# SCH_SCore-SR1_2024-11-10.net
KiCad netlist of a schematic drawn in EasyEDA
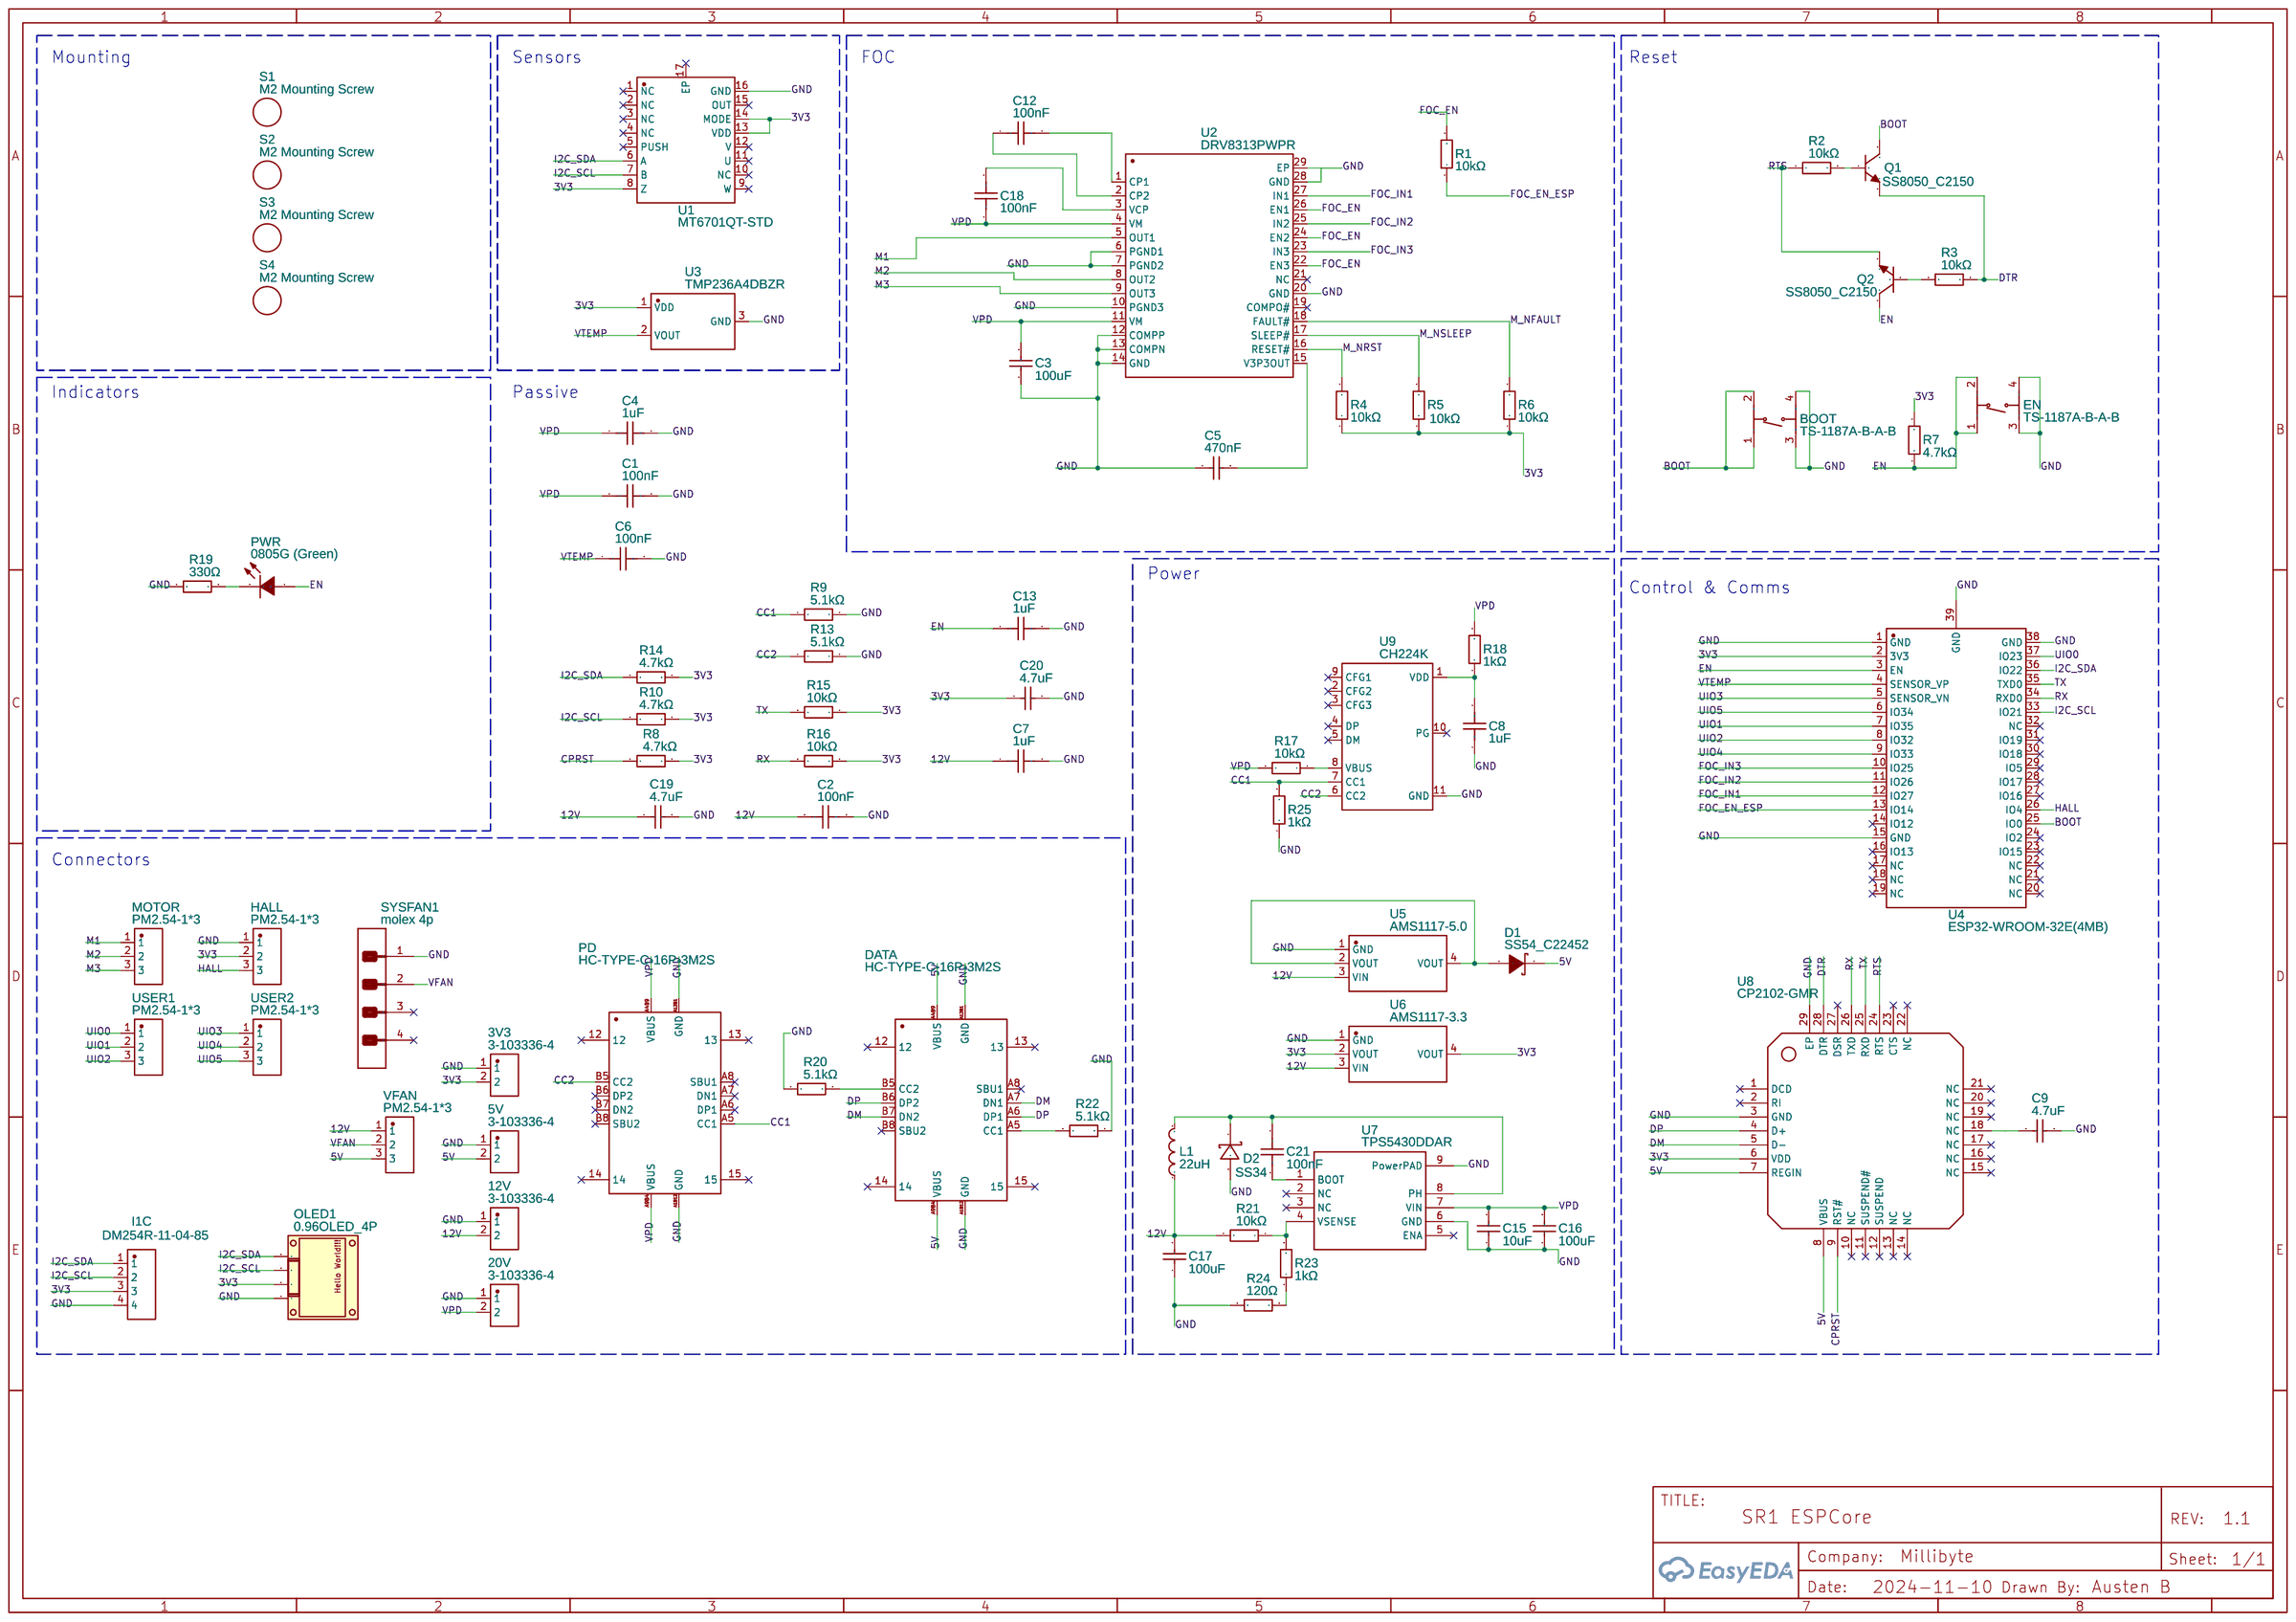
[diagram p0: schematic sheet]

(export (version "E")
  (design (tool "Eeschema 10.0.6"))
  (components
    (comp (ref "3V3")
      (value "3-103336-4")
      (fields (field (name "Manufacturer") "TE Connectivity(泰科电子)"))
      (libsource (lib "") (part "3-103336-4"))
    )
    (comp (ref "5V")
      (value "3-103336-4")
      (fields (field (name "Manufacturer") "TE Connectivity(泰科电子)"))
      (libsource (lib "") (part "3-103336-4_3"))
    )
    (comp (ref "12V")
      (value "3-103336-4")
      (fields (field (name "Manufacturer") "TE Connectivity(泰科电子)"))
      (libsource (lib "") (part "3-103336-4_1"))
    )
    (comp (ref "20V")
      (value "3-103336-4")
      (fields (field (name "Manufacturer") "TE Connectivity(泰科电子)"))
      (libsource (lib "") (part "3-103336-4_2"))
    )
    (comp (ref "BOOT")
      (value "TS-1187A-B-A-B")
      (fields (field (name "Manufacturer") "XKB Connectivity(中国星坤)"))
      (libsource (lib "") (part "TS-1187A-B-A-B"))
    )
    (comp (ref "C1")
      (value "100nF")
      (fields
        (field (name "Manufacturer Part") "CC0603KRX7R9BB104")
        (field (name "Manufacturer") "YAGEO(国巨)")
      )
      (libsource (lib "") (part "CC0603KRX7R9BB104"))
    )
    (comp (ref "C2")
      (value "100nF")
      (fields
        (field (name "Manufacturer Part") "CC0603KRX7R9BB104")
        (field (name "Manufacturer") "YAGEO(国巨)")
      )
      (libsource (lib "") (part "CC0603KRX7R9BB104"))
    )
    (comp (ref "C3")
      (value "100uF")
      (fields
        (field (name "Manufacturer Part") "CL31A107MQHNNNE")
        (field (name "Manufacturer") "SAMSUNG(三星)")
      )
      (libsource (lib "") (part "CL31A107MQHNNNE"))
    )
    (comp (ref "C4")
      (value "1uF")
      (fields
        (field (name "Manufacturer Part") "CL10A105KB8NNNC")
        (field (name "Manufacturer") "SAMSUNG(三星)")
      )
      (libsource (lib "") (part "CL10A105KB8NNNC_1"))
    )
    (comp (ref "C5")
      (value "470nF")
      (fields
        (field (name "Manufacturer Part") "CL21B474KBFNNNE")
        (field (name "Manufacturer") "SAMSUNG(三星)")
      )
      (libsource (lib "") (part "CL21B474KBFNNNE"))
    )
    (comp (ref "C6")
      (value "100nF")
      (fields
        (field (name "Manufacturer Part") "CC0603KRX7R9BB104")
        (field (name "Manufacturer") "YAGEO(国巨)")
      )
      (libsource (lib "") (part "CC0603KRX7R9BB104"))
    )
    (comp (ref "C7")
      (value "1uF")
      (fields
        (field (name "Manufacturer Part") "CL10A105KB8NNNC")
        (field (name "Manufacturer") "SAMSUNG(三星)")
      )
      (libsource (lib "") (part "CL10A105KB8NNNC_1"))
    )
    (comp (ref "C8")
      (value "1uF")
      (fields
        (field (name "Manufacturer Part") "CL10A105KB8NNNC")
        (field (name "Manufacturer") "SAMSUNG(三星)")
      )
      (libsource (lib "") (part "CL10A105KB8NNNC"))
    )
    (comp (ref "C9")
      (value "4.7uF")
      (fields
        (field (name "Manufacturer Part") "CL21A475KAQNNNE")
        (field (name "Manufacturer") "SAMSUNG(三星)")
      )
      (libsource (lib "") (part "CL21A475KAQNNNE"))
    )
    (comp (ref "C12")
      (value "100nF")
      (fields
        (field (name "Manufacturer Part") "CC0603KRX7R9BB104")
        (field (name "Manufacturer") "YAGEO(国巨)")
      )
      (libsource (lib "") (part "CC0603KRX7R9BB104"))
    )
    (comp (ref "C13")
      (value "1uF")
      (fields
        (field (name "Manufacturer Part") "CL10A105KB8NNNC")
        (field (name "Manufacturer") "SAMSUNG(三星)")
      )
      (libsource (lib "") (part "CL10A105KB8NNNC_1"))
    )
    (comp (ref "C15")
      (value "10uF")
      (fields
        (field (name "Manufacturer Part") "CL31A106KBHNNNE")
        (field (name "Manufacturer") "SAMSUNG(三星)")
      )
      (libsource (lib "") (part "CL31A106KBHNNNE"))
    )
    (comp (ref "C16")
      (value "100uF")
      (fields
        (field (name "Manufacturer Part") "CL31A107MQHNNNE")
        (field (name "Manufacturer") "SAMSUNG(三星)")
      )
      (libsource (lib "") (part "CL31A107MQHNNNE"))
    )
    (comp (ref "C17")
      (value "100uF")
      (fields
        (field (name "Manufacturer Part") "CL31A107MQHNNNE")
        (field (name "Manufacturer") "SAMSUNG(三星)")
      )
      (libsource (lib "") (part "CL31A107MQHNNNE"))
    )
    (comp (ref "C18")
      (value "100nF")
      (fields
        (field (name "Manufacturer Part") "CC0603KRX7R9BB104")
        (field (name "Manufacturer") "YAGEO(国巨)")
      )
      (libsource (lib "") (part "CC0603KRX7R9BB104_2"))
    )
    (comp (ref "C19")
      (value "4.7uF")
      (fields
        (field (name "Manufacturer Part") "CL21A475KAQNNNE")
        (field (name "Manufacturer") "SAMSUNG(三星)")
      )
      (libsource (lib "") (part "CL21A475KAQNNNE"))
    )
    (comp (ref "C20")
      (value "4.7uF")
      (fields
        (field (name "Manufacturer Part") "CL21A475KAQNNNE")
        (field (name "Manufacturer") "SAMSUNG(三星)")
      )
      (libsource (lib "") (part "CL21A475KAQNNNE"))
    )
    (comp (ref "C21")
      (value "100nF")
      (fields
        (field (name "Manufacturer Part") "CC0603KRX7R9BB104")
        (field (name "Manufacturer") "YAGEO(国巨)")
      )
      (libsource (lib "") (part "CC0603KRX7R9BB104_1"))
    )
    (comp (ref "D1")
      (value "SS54_C22452")
      (fields (field (name "Manufacturer Part") "SS54") (field (name "Manufacturer") "MDD"))
      (libsource (lib "") (part "SS54_C22452"))
    )
    (comp (ref "D2")
      (value "SS34")
      (fields (field (name "Manufacturer") "MDD(辰达半导体)"))
      (libsource (lib "") (part "SS34_C8678"))
    )
    (comp (ref "DATA")
      (value "HC-TYPE-C-16P-3M2S")
      (fields (field (name "Manufacturer") "HC(虹成电子)"))
      (libsource (lib "") (part "HC-TYPE-C-16P-3M2S"))
    )
    (comp (ref "EN")
      (value "TS-1187A-B-A-B")
      (fields (field (name "Manufacturer") "XKB Connectivity(中国星坤)"))
      (libsource (lib "") (part "TS-1187A-B-A-B_1"))
    )
    (comp (ref "HALL")
      (value "PM2.54-1*3")
      (fields (field (name "Manufacturer") "ZHOURI(洲日)"))
      (libsource (lib "") (part "PM2.54-1*3"))
    )
    (comp (ref "I1C")
      (value "DM254R-11-04-85")
      (fields (field (name "Manufacturer") "DEALON(德艺隆)"))
      (libsource (lib "") (part "DM254R-11-04-85"))
    )
    (comp (ref "L1")
      (value "22uH")
      (fields (field (name "Manufacturer Part") "PRS4018-220MT") (field (name "Manufacturer") "FH(风华)"))
      (libsource (lib "") (part "PRS4018-220MT"))
    )
    (comp (ref "MOTOR")
      (value "PM2.54-1*3")
      (fields (field (name "Manufacturer") "ZHOURI(洲日)"))
      (libsource (lib "") (part "PM2.54-1*3_3"))
    )
    (comp (ref "OLED1") (value "0.96OLED_4P") (libsource (lib "") (part "0.96OLED_4P")))
    (comp (ref "PD")
      (value "HC-TYPE-C-16P-3M2S")
      (fields (field (name "Manufacturer") "HC(虹成电子)"))
      (libsource (lib "") (part "HC-TYPE-C-16P-3M2S_1"))
    )
    (comp (ref "PWR")
      (value "0805G (Green)")
      (fields (field (name "Manufacturer Part") "KT-0805G") (field (name "Manufacturer") "KENTO"))
      (libsource (lib "") (part "0805G (Green)"))
    )
    (comp (ref "Q1")
      (value "SS8050_C2150")
      (fields (field (name "Manufacturer Part") "SS8050") (field (name "Manufacturer") "CJ(江苏长电/长晶)"))
      (libsource (lib "") (part "SS8050_C2150"))
    )
    (comp (ref "Q2")
      (value "SS8050_C2150")
      (fields (field (name "Manufacturer Part") "SS8050") (field (name "Manufacturer") "CJ(江苏长电/长晶)"))
      (libsource (lib "") (part "SS8050_C2150_1"))
    )
    (comp (ref "R1")
      (value "10kΩ")
      (fields (field (name "Manufacturer Part") "0603WAF4701T5E") (field (name "Manufacturer") "UniOhm"))
      (libsource (lib "") (part "0603WAF4701T5E_1"))
    )
    (comp (ref "R2")
      (value "10kΩ")
      (fields
        (field (name "Manufacturer Part") "1206W4F1002T5E")
        (field (name "Manufacturer") "UNI-ROYAL(厚声)")
      )
      (libsource (lib "") (part "1206W4F1002T5E"))
    )
    (comp (ref "R3")
      (value "10kΩ")
      (fields
        (field (name "Manufacturer Part") "1206W4F1002T5E")
        (field (name "Manufacturer") "UNI-ROYAL(厚声)")
      )
      (libsource (lib "") (part "1206W4F1002T5E"))
    )
    (comp (ref "R4")
      (value "10kΩ")
      (fields (field (name "Manufacturer Part") "0603WAF4701T5E") (field (name "Manufacturer") "UniOhm"))
      (libsource (lib "") (part "0603WAF4701T5E_1"))
    )
    (comp (ref "R5")
      (value "10kΩ")
      (fields (field (name "Manufacturer Part") "0603WAF4701T5E") (field (name "Manufacturer") "UniOhm"))
      (libsource (lib "") (part "0603WAF4701T5E_1"))
    )
    (comp (ref "R6")
      (value "10kΩ")
      (fields (field (name "Manufacturer Part") "0603WAF4701T5E") (field (name "Manufacturer") "UniOhm"))
      (libsource (lib "") (part "0603WAF4701T5E_1"))
    )
    (comp (ref "R7")
      (value "4.7kΩ")
      (fields
        (field (name "Manufacturer Part") "0805W8F4701T5E")
        (field (name "Manufacturer") "UNI-ROYAL(厚声)")
      )
      (libsource (lib "") (part "0805W8F4701T5E_1"))
    )
    (comp (ref "R8")
      (value "4.7kΩ")
      (fields
        (field (name "Manufacturer Part") "0805W8F4701T5E")
        (field (name "Manufacturer") "UNI-ROYAL(厚声)")
      )
      (libsource (lib "") (part "0805W8F4701T5E"))
    )
    (comp (ref "R9")
      (value "5.1kΩ")
      (fields
        (field (name "Manufacturer Part") "0603WAF5101T5E")
        (field (name "Manufacturer") "UNI-ROYAL(厚声)")
      )
      (libsource (lib "") (part "0603WAF5101T5E"))
    )
    (comp (ref "R10")
      (value "4.7kΩ")
      (fields
        (field (name "Manufacturer Part") "0805W8F4701T5E")
        (field (name "Manufacturer") "UNI-ROYAL(厚声)")
      )
      (libsource (lib "") (part "0805W8F4701T5E"))
    )
    (comp (ref "R13")
      (value "5.1kΩ")
      (fields
        (field (name "Manufacturer Part") "0603WAF5101T5E")
        (field (name "Manufacturer") "UNI-ROYAL(厚声)")
      )
      (libsource (lib "") (part "0603WAF5101T5E"))
    )
    (comp (ref "R14")
      (value "4.7kΩ")
      (fields
        (field (name "Manufacturer Part") "0805W8F4701T5E")
        (field (name "Manufacturer") "UNI-ROYAL(厚声)")
      )
      (libsource (lib "") (part "0805W8F4701T5E"))
    )
    (comp (ref "R15")
      (value "10kΩ")
      (fields (field (name "Manufacturer Part") "0603WAF4701T5E") (field (name "Manufacturer") "UniOhm"))
      (libsource (lib "") (part "0603WAF4701T5E"))
    )
    (comp (ref "R16")
      (value "10kΩ")
      (fields (field (name "Manufacturer Part") "0603WAF4701T5E") (field (name "Manufacturer") "UniOhm"))
      (libsource (lib "") (part "0603WAF4701T5E"))
    )
    (comp (ref "R17")
      (value "10kΩ")
      (fields (field (name "Manufacturer Part") "0603WAF4701T5E") (field (name "Manufacturer") "UniOhm"))
      (libsource (lib "") (part "0603WAF4701T5E"))
    )
    (comp (ref "R18")
      (value "1kΩ")
      (fields
        (field (name "Manufacturer Part") "0402WGF1001TCE")
        (field (name "Manufacturer") "UNI-ROYAL(厚声)")
      )
      (libsource (lib "") (part "0402WGF1001TCE"))
    )
    (comp (ref "R19")
      (value "330Ω")
      (fields
        (field (name "Manufacturer Part") "0805W8F3300T5E")
        (field (name "Manufacturer") "UNI-ROYAL(厚声)")
      )
      (libsource (lib "") (part "0805W8F3300T5E"))
    )
    (comp (ref "R20")
      (value "5.1kΩ")
      (fields
        (field (name "Manufacturer Part") "0603WAF5101T5E")
        (field (name "Manufacturer") "UNI-ROYAL(厚声)")
      )
      (libsource (lib "") (part "0603WAF5101T5E"))
    )
    (comp (ref "R21")
      (value "10kΩ")
      (fields
        (field (name "Manufacturer Part") "0805W8F1002T5E")
        (field (name "Manufacturer") "UNI-ROYAL(厚声)")
      )
      (libsource (lib "") (part "0805W8F1002T5E"))
    )
    (comp (ref "R22")
      (value "5.1kΩ")
      (fields
        (field (name "Manufacturer Part") "0603WAF5101T5E")
        (field (name "Manufacturer") "UNI-ROYAL(厚声)")
      )
      (libsource (lib "") (part "0603WAF5101T5E"))
    )
    (comp (ref "R23")
      (value "1kΩ")
      (fields
        (field (name "Manufacturer Part") "0402WGF1001TCE")
        (field (name "Manufacturer") "UNI-ROYAL(厚声)")
      )
      (libsource (lib "") (part "0402WGF1001TCE"))
    )
    (comp (ref "R24")
      (value "120Ω")
      (fields
        (field (name "Manufacturer Part") "0805W8F1200T5E")
        (field (name "Manufacturer") "UNI-ROYAL(厚声)")
      )
      (libsource (lib "") (part "0805W8F1200T5E"))
    )
    (comp (ref "R25")
      (value "1kΩ")
      (fields
        (field (name "Manufacturer Part") "0402WGF1001TCE")
        (field (name "Manufacturer") "UNI-ROYAL(厚声)")
      )
      (libsource (lib "") (part "0402WGF1001TCE"))
    )
    (comp (ref "S1") (value "M2 Mounting Screw") (libsource (lib "") (part "M2 Mounting Screw")))
    (comp (ref "S2") (value "M2 Mounting Screw") (libsource (lib "") (part "M2 Mounting Screw")))
    (comp (ref "S3") (value "M2 Mounting Screw") (libsource (lib "") (part "M2 Mounting Screw")))
    (comp (ref "S4") (value "M2 Mounting Screw") (libsource (lib "") (part "M2 Mounting Screw")))
    (comp (ref "SYSFAN1") (value "molex 4p") (libsource (lib "") (part "molex 4p")))
    (comp (ref "U1")
      (value "MT6701QT-STD")
      (fields (field (name "Manufacturer") "MagnTek(麦歌恩)"))
      (libsource (lib "") (part "MT6701QT-STD"))
    )
    (comp (ref "U2")
      (value "DRV8313PWPR")
      (fields (field (name "Manufacturer") "Texas Instruments"))
      (libsource (lib "") (part "DRV8313PWPR"))
    )
    (comp (ref "U3")
      (value "TMP236A4DBZR")
      (fields (field (name "Manufacturer") "TI(德州仪器)"))
      (libsource (lib "") (part "TMP236A4DBZR"))
    )
    (comp (ref "U4")
      (value "ESP32-WROOM-32E(4MB)")
      (fields
        (field (name "Manufacturer Part") "ESP32-WROOM-32E-N4")
        (field (name "Manufacturer") "ESPRESSIF(乐鑫)")
      )
      (libsource (lib "") (part "ESP32-WROOM-32E(4MB)"))
    )
    (comp (ref "U5")
      (value "AMS1117-5.0")
      (fields (field (name "Manufacturer") "AMS"))
      (libsource (lib "") (part "AMS1117-5.0"))
    )
    (comp (ref "U6")
      (value "AMS1117-3.3")
      (fields (field (name "Manufacturer") "AMS"))
      (libsource (lib "") (part "AMS1117-3.3"))
    )
    (comp (ref "U7")
      (value "TPS5430DDAR")
      (fields (field (name "Manufacturer") "TI(德州仪器)"))
      (libsource (lib "") (part "TPS5430DDAR"))
    )
    (comp (ref "U8")
      (value "CP2102-GMR")
      (fields (field (name "Manufacturer") "SKYWORKS/SILICON LABS(芯科)"))
      (libsource (lib "") (part "CP2102-GMR"))
    )
    (comp (ref "U9")
      (value "CH224K")
      (fields (field (name "Manufacturer") "WCH(南京沁恒)"))
      (libsource (lib "") (part "CH224K"))
    )
    (comp (ref "USER1")
      (value "PM2.54-1*3")
      (fields (field (name "Manufacturer") "ZHOURI(洲日)"))
      (libsource (lib "") (part "PM2.54-1*3_2"))
    )
    (comp (ref "USER2")
      (value "PM2.54-1*3")
      (fields (field (name "Manufacturer") "ZHOURI(洲日)"))
      (libsource (lib "") (part "PM2.54-1*3_2"))
    )
    (comp (ref "VFAN")
      (value "PM2.54-1*3")
      (fields (field (name "Manufacturer") "ZHOURI(洲日)"))
      (libsource (lib "") (part "PM2.54-1*3_1"))
    )
  )
  (nets
    (net (code "1") (name "/3V3") (class "Default")
      (node (ref "3V3") (pin "2") (pinfunction "2_2") (pintype "unspecified"))
      (node (ref "C20") (pin "1") (pinfunction "1_1") (pintype "input"))
      (node (ref "HALL") (pin "2") (pinfunction "2_2") (pintype "unspecified"))
      (node (ref "I1C") (pin "3") (pinfunction "3_3") (pintype "unspecified"))
      (node (ref "OLED1") (pin "3") (pinfunction "3_3") (pintype "unspecified"))
      (node (ref "R10") (pin "1") (pinfunction "1_1") (pintype "input"))
      (node (ref "R14") (pin "1") (pinfunction "1_1") (pintype "input"))
      (node (ref "R15") (pin "1") (pinfunction "1_1") (pintype "input"))
      (node (ref "R16") (pin "1") (pinfunction "1_1") (pintype "input"))
      (node (ref "R4") (pin "1") (pinfunction "1_1") (pintype "input"))
      (node (ref "R5") (pin "1") (pinfunction "1_1") (pintype "input"))
      (node (ref "R6") (pin "1") (pinfunction "1_1") (pintype "input"))
      (node (ref "R7") (pin "2") (pinfunction "2_2") (pintype "input"))
      (node (ref "R8") (pin "1") (pinfunction "1_1") (pintype "input"))
      (node (ref "U1") (pin "13") (pinfunction "VDD_13") (pintype "unspecified"))
      (node (ref "U1") (pin "14") (pinfunction "MODE_14") (pintype "unspecified"))
      (node (ref "U1") (pin "8") (pinfunction "Z_8") (pintype "unspecified"))
      (node (ref "U3") (pin "1") (pinfunction "VDD_1") (pintype "unspecified"))
      (node (ref "U4") (pin "2") (pinfunction "3V3_2") (pintype "unspecified"))
      (node (ref "U6") (pin "2") (pinfunction "VOUT_2") (pintype "unspecified"))
      (node (ref "U6") (pin "4") (pinfunction "VOUT_4") (pintype "unspecified"))
      (node (ref "U8") (pin "6") (pinfunction "VDD_6") (pintype "unspecified"))
    )
    (net (code "2") (name "/5V") (class "Default")
      (node (ref "5V") (pin "2") (pinfunction "2_2") (pintype "unspecified"))
      (node (ref "D1") (pin "2") (pinfunction "K_2") (pintype "unspecified"))
      (node (ref "DATA") (pin "A4B9") (pinfunction "VBUS_A4B9") (pintype "unspecified"))
      (node (ref "DATA") (pin "A9B4") (pinfunction "VBUS_A9B4") (pintype "unspecified"))
      (node (ref "U8") (pin "7") (pinfunction "REGIN_7") (pintype "unspecified"))
      (node (ref "U8") (pin "8") (pinfunction "VBUS_8") (pintype "unspecified"))
      (node (ref "VFAN") (pin "3") (pinfunction "3_3") (pintype "unspecified"))
    )
    (net (code "3") (name "/12V") (class "Default")
      (node (ref "12V") (pin "2") (pinfunction "2_2") (pintype "unspecified"))
      (node (ref "C17") (pin "2") (pinfunction "2_2") (pintype "input"))
      (node (ref "C19") (pin "1") (pinfunction "1_1") (pintype "input"))
      (node (ref "C2") (pin "1") (pinfunction "1_1") (pintype "unspecified"))
      (node (ref "C7") (pin "1") (pinfunction "1_1") (pintype "unspecified"))
      (node (ref "L1") (pin "1") (pinfunction "1_1") (pintype "unspecified"))
      (node (ref "R21") (pin "2") (pinfunction "2_2") (pintype "input"))
      (node (ref "U5") (pin "3") (pinfunction "VIN_3") (pintype "unspecified"))
      (node (ref "U6") (pin "3") (pinfunction "VIN_3") (pintype "unspecified"))
      (node (ref "VFAN") (pin "1") (pinfunction "1_1") (pintype "unspecified"))
    )
    (net (code "4") (name "/BOOT") (class "Default")
      (node (ref "BOOT") (pin "1") (pinfunction "A_1") (pintype "unspecified"))
      (node (ref "BOOT") (pin "2") (pinfunction "B_2") (pintype "unspecified"))
      (node (ref "Q1") (pin "3") (pinfunction "C_3") (pintype "unspecified"))
      (node (ref "U4") (pin "25") (pinfunction "IO0_25") (pintype "unspecified"))
    )
    (net (code "5") (name "/CC1") (class "Default")
      (node (ref "PD") (pin "A5") (pinfunction "CC1_A5") (pintype "unspecified"))
      (node (ref "R25") (pin "2") (pinfunction "2_2") (pintype "input"))
      (node (ref "R9") (pin "1") (pinfunction "1_1") (pintype "input"))
      (node (ref "U9") (pin "7") (pinfunction "CC1_7") (pintype "unspecified"))
    )
    (net (code "6") (name "/CC2") (class "Default")
      (node (ref "PD") (pin "B5") (pinfunction "CC2_B5") (pintype "unspecified"))
      (node (ref "R13") (pin "1") (pinfunction "1_1") (pintype "input"))
      (node (ref "U9") (pin "6") (pinfunction "CC2_6") (pintype "unspecified"))
    )
    (net (code "7") (name "/CPRST") (class "Default")
      (node (ref "R8") (pin "2") (pinfunction "2_2") (pintype "input"))
      (node (ref "U8") (pin "9") (pinfunction "RST#_9") (pintype "unspecified"))
    )
    (net (code "8") (name "/DM") (class "Default")
      (node (ref "DATA") (pin "A7") (pinfunction "DN1_A7") (pintype "unspecified"))
      (node (ref "DATA") (pin "B7") (pinfunction "DN2_B7") (pintype "unspecified"))
      (node (ref "U8") (pin "5") (pinfunction "D-_5") (pintype "unspecified"))
    )
    (net (code "9") (name "/DP") (class "Default")
      (node (ref "DATA") (pin "A6") (pinfunction "DP1_A6") (pintype "unspecified"))
      (node (ref "DATA") (pin "B6") (pinfunction "DP2_B6") (pintype "unspecified"))
      (node (ref "U8") (pin "4") (pinfunction "D+_4") (pintype "unspecified"))
    )
    (net (code "10") (name "/DTR") (class "Default")
      (node (ref "Q1") (pin "2") (pinfunction "E_2") (pintype "unspecified"))
      (node (ref "R3") (pin "2") (pinfunction "2_2") (pintype "input"))
      (node (ref "U8") (pin "28") (pinfunction "DTR_28") (pintype "unspecified"))
    )
    (net (code "11") (name "/EN") (class "Default")
      (node (ref "C13") (pin "1") (pinfunction "1_1") (pintype "unspecified"))
      (node (ref "EN") (pin "1") (pinfunction "A_1") (pintype "unspecified"))
      (node (ref "EN") (pin "2") (pinfunction "B_2") (pintype "unspecified"))
      (node (ref "PWR") (pin "1") (pinfunction "A_1") (pintype "unspecified"))
      (node (ref "Q2") (pin "3") (pinfunction "C_3") (pintype "unspecified"))
      (node (ref "R7") (pin "1") (pinfunction "1_1") (pintype "input"))
      (node (ref "U4") (pin "3") (pinfunction "EN_3") (pintype "unspecified"))
    )
    (net (code "12") (name "/FOC_EN") (class "Default")
      (node (ref "R1") (pin "2") (pinfunction "2_2") (pintype "input"))
      (node (ref "U2") (pin "22") (pinfunction "EN3_22") (pintype "unspecified"))
      (node (ref "U2") (pin "24") (pinfunction "EN2_24") (pintype "unspecified"))
      (node (ref "U2") (pin "26") (pinfunction "EN1_26") (pintype "unspecified"))
    )
    (net (code "13") (name "/FOC_EN_ESP") (class "Default")
      (node (ref "R1") (pin "1") (pinfunction "1_1") (pintype "input"))
      (node (ref "U4") (pin "13") (pinfunction "IO14_13") (pintype "unspecified"))
    )
    (net (code "14") (name "/FOC_IN1") (class "Default")
      (node (ref "U2") (pin "27") (pinfunction "IN1_27") (pintype "unspecified"))
      (node (ref "U4") (pin "12") (pinfunction "IO27_12") (pintype "unspecified"))
    )
    (net (code "15") (name "/FOC_IN2") (class "Default")
      (node (ref "U2") (pin "25") (pinfunction "IN2_25") (pintype "unspecified"))
      (node (ref "U4") (pin "11") (pinfunction "IO26_11") (pintype "unspecified"))
    )
    (net (code "16") (name "/FOC_IN3") (class "Default")
      (node (ref "U2") (pin "23") (pinfunction "IN3_23") (pintype "unspecified"))
      (node (ref "U4") (pin "10") (pinfunction "IO25_10") (pintype "unspecified"))
    )
    (net (code "17") (name "/GND") (class "Default")
      (node (ref "12V") (pin "1") (pinfunction "1_1") (pintype "unspecified"))
      (node (ref "20V") (pin "1") (pinfunction "1_1") (pintype "unspecified"))
      (node (ref "3V3") (pin "1") (pinfunction "1_1") (pintype "unspecified"))
      (node (ref "5V") (pin "1") (pinfunction "1_1") (pintype "unspecified"))
      (node (ref "BOOT") (pin "3") (pinfunction "C_3") (pintype "unspecified"))
      (node (ref "BOOT") (pin "4") (pinfunction "D_4") (pintype "unspecified"))
      (node (ref "C1") (pin "2") (pinfunction "2_2") (pintype "unspecified"))
      (node (ref "C13") (pin "2") (pinfunction "2_2") (pintype "unspecified"))
      (node (ref "C15") (pin "1") (pinfunction "1_1") (pintype "input"))
      (node (ref "C16") (pin "1") (pinfunction "1_1") (pintype "input"))
      (node (ref "C17") (pin "1") (pinfunction "1_1") (pintype "input"))
      (node (ref "C19") (pin "2") (pinfunction "2_2") (pintype "input"))
      (node (ref "C2") (pin "2") (pinfunction "2_2") (pintype "unspecified"))
      (node (ref "C20") (pin "2") (pinfunction "2_2") (pintype "input"))
      (node (ref "C3") (pin "1") (pinfunction "1_1") (pintype "input"))
      (node (ref "C4") (pin "2") (pinfunction "2_2") (pintype "unspecified"))
      (node (ref "C5") (pin "1") (pinfunction "1_1") (pintype "unspecified"))
      (node (ref "C6") (pin "2") (pinfunction "2_2") (pintype "unspecified"))
      (node (ref "C7") (pin "2") (pinfunction "2_2") (pintype "unspecified"))
      (node (ref "C8") (pin "1") (pinfunction "1_1") (pintype "unspecified"))
      (node (ref "C9") (pin "2") (pinfunction "2_2") (pintype "input"))
      (node (ref "D2") (pin "2") (pinfunction "A_2") (pintype "unspecified"))
      (node (ref "DATA") (pin "A12B1") (pinfunction "GND_A12B1") (pintype "unspecified"))
      (node (ref "DATA") (pin "A1B12") (pinfunction "GND_A1B12") (pintype "unspecified"))
      (node (ref "EN") (pin "3") (pinfunction "C_3") (pintype "unspecified"))
      (node (ref "EN") (pin "4") (pinfunction "D_4") (pintype "unspecified"))
      (node (ref "HALL") (pin "1") (pinfunction "1_1") (pintype "unspecified"))
      (node (ref "I1C") (pin "4") (pinfunction "4_4") (pintype "unspecified"))
      (node (ref "OLED1") (pin "4") (pinfunction "4_4") (pintype "unspecified"))
      (node (ref "PD") (pin "A12B1") (pinfunction "GND_A12B1") (pintype "unspecified"))
      (node (ref "PD") (pin "A1B12") (pinfunction "GND_A1B12") (pintype "unspecified"))
      (node (ref "R13") (pin "2") (pinfunction "2_2") (pintype "input"))
      (node (ref "R19") (pin "1") (pinfunction "1_1") (pintype "input"))
      (node (ref "R20") (pin "1") (pinfunction "1_1") (pintype "input"))
      (node (ref "R22") (pin "2") (pinfunction "2_2") (pintype "input"))
      (node (ref "R24") (pin "1") (pinfunction "1_1") (pintype "input"))
      (node (ref "R25") (pin "1") (pinfunction "1_1") (pintype "input"))
      (node (ref "R9") (pin "2") (pinfunction "2_2") (pintype "input"))
      (node (ref "SYSFAN1") (pin "1") (pinfunction "1_1") (pintype "bidirectional"))
      (node (ref "U1") (pin "16") (pinfunction "GND_16") (pintype "unspecified"))
      (node (ref "U2") (pin "10") (pinfunction "PGND3_10") (pintype "unspecified"))
      (node (ref "U2") (pin "12") (pinfunction "COMPP_12") (pintype "unspecified"))
      (node (ref "U2") (pin "13") (pinfunction "COMPN_13") (pintype "unspecified"))
      (node (ref "U2") (pin "14") (pinfunction "GND_14") (pintype "unspecified"))
      (node (ref "U2") (pin "20") (pinfunction "GND_20") (pintype "unspecified"))
      (node (ref "U2") (pin "28") (pinfunction "GND_28") (pintype "unspecified"))
      (node (ref "U2") (pin "29") (pinfunction "EP_29") (pintype "unspecified"))
      (node (ref "U2") (pin "6") (pinfunction "PGND1_6") (pintype "unspecified"))
      (node (ref "U2") (pin "7") (pinfunction "PGND2_7") (pintype "unspecified"))
      (node (ref "U3") (pin "3") (pinfunction "GND_3") (pintype "unspecified"))
      (node (ref "U4") (pin "1") (pinfunction "GND_1") (pintype "unspecified"))
      (node (ref "U4") (pin "15") (pinfunction "GND_15") (pintype "unspecified"))
      (node (ref "U4") (pin "38") (pinfunction "GND_38") (pintype "unspecified"))
      (node (ref "U4") (pin "39") (pinfunction "GND_39") (pintype "unspecified"))
      (node (ref "U5") (pin "1") (pinfunction "GND_1") (pintype "unspecified"))
      (node (ref "U6") (pin "1") (pinfunction "GND_1") (pintype "unspecified"))
      (node (ref "U7") (pin "6") (pinfunction "GND_6") (pintype "unspecified"))
      (node (ref "U7") (pin "9") (pinfunction "PowerPAD_9") (pintype "unspecified"))
      (node (ref "U8") (pin "29") (pinfunction "EP_29") (pintype "unspecified"))
      (node (ref "U8") (pin "3") (pinfunction "GND_3") (pintype "unspecified"))
      (node (ref "U9") (pin "11") (pinfunction "GND_11") (pintype "unspecified"))
    )
    (net (code "18") (name "/HALL") (class "Default")
      (node (ref "HALL") (pin "3") (pinfunction "3_3") (pintype "unspecified"))
      (node (ref "U4") (pin "26") (pinfunction "IO4_26") (pintype "unspecified"))
    )
    (net (code "19") (name "/I2C_SCL") (class "Default")
      (node (ref "I1C") (pin "2") (pinfunction "2_2") (pintype "unspecified"))
      (node (ref "OLED1") (pin "2") (pinfunction "2_2") (pintype "unspecified"))
      (node (ref "R10") (pin "2") (pinfunction "2_2") (pintype "input"))
      (node (ref "U1") (pin "7") (pinfunction "B_7") (pintype "unspecified"))
      (node (ref "U4") (pin "33") (pinfunction "IO21_33") (pintype "unspecified"))
    )
    (net (code "20") (name "/I2C_SDA") (class "Default")
      (node (ref "I1C") (pin "1") (pinfunction "1_1") (pintype "unspecified"))
      (node (ref "OLED1") (pin "1") (pinfunction "1_1") (pintype "unspecified"))
      (node (ref "R14") (pin "2") (pinfunction "2_2") (pintype "input"))
      (node (ref "U1") (pin "6") (pinfunction "A_6") (pintype "unspecified"))
      (node (ref "U4") (pin "36") (pinfunction "IO22_36") (pintype "unspecified"))
    )
    (net (code "21") (name "/M1") (class "Default")
      (node (ref "MOTOR") (pin "1") (pinfunction "1_1") (pintype "unspecified"))
      (node (ref "U2") (pin "5") (pinfunction "OUT1_5") (pintype "unspecified"))
    )
    (net (code "22") (name "/M2") (class "Default")
      (node (ref "MOTOR") (pin "2") (pinfunction "2_2") (pintype "unspecified"))
      (node (ref "U2") (pin "8") (pinfunction "OUT2_8") (pintype "unspecified"))
    )
    (net (code "23") (name "/M3") (class "Default")
      (node (ref "MOTOR") (pin "3") (pinfunction "3_3") (pintype "unspecified"))
      (node (ref "U2") (pin "9") (pinfunction "OUT3_9") (pintype "unspecified"))
    )
    (net (code "24") (name "/M_NFAULT") (class "Default")
      (node (ref "R6") (pin "2") (pinfunction "2_2") (pintype "input"))
      (node (ref "U2") (pin "18") (pinfunction "FAULT#_18") (pintype "unspecified"))
    )
    (net (code "25") (name "/M_NRST") (class "Default")
      (node (ref "R4") (pin "2") (pinfunction "2_2") (pintype "input"))
      (node (ref "U2") (pin "16") (pinfunction "RESET#_16") (pintype "unspecified"))
    )
    (net (code "26") (name "/M_NSLEEP") (class "Default")
      (node (ref "R5") (pin "2") (pinfunction "2_2") (pintype "input"))
      (node (ref "U2") (pin "17") (pinfunction "SLEEP#_17") (pintype "unspecified"))
    )
    (net (code "27") (name "/RTS") (class "Default")
      (node (ref "Q2") (pin "2") (pinfunction "E_2") (pintype "unspecified"))
      (node (ref "R2") (pin "1") (pinfunction "1_1") (pintype "input"))
      (node (ref "U8") (pin "24") (pinfunction "RTS_24") (pintype "unspecified"))
    )
    (net (code "28") (name "/RX") (class "Default")
      (node (ref "R16") (pin "2") (pinfunction "2_2") (pintype "input"))
      (node (ref "U4") (pin "34") (pinfunction "RXD0_34") (pintype "unspecified"))
      (node (ref "U8") (pin "26") (pinfunction "TXD_26") (pintype "unspecified"))
    )
    (net (code "29") (name "/TX") (class "Default")
      (node (ref "R15") (pin "2") (pinfunction "2_2") (pintype "input"))
      (node (ref "U4") (pin "35") (pinfunction "TXD0_35") (pintype "unspecified"))
      (node (ref "U8") (pin "25") (pinfunction "RXD_25") (pintype "unspecified"))
    )
    (net (code "30") (name "/UIO0") (class "Default")
      (node (ref "U4") (pin "37") (pinfunction "IO23_37") (pintype "unspecified"))
      (node (ref "USER1") (pin "1") (pinfunction "1_1") (pintype "unspecified"))
    )
    (net (code "31") (name "/UIO1") (class "Default")
      (node (ref "U4") (pin "7") (pinfunction "IO35_7") (pintype "unspecified"))
      (node (ref "USER1") (pin "2") (pinfunction "2_2") (pintype "unspecified"))
    )
    (net (code "32") (name "/UIO2") (class "Default")
      (node (ref "U4") (pin "8") (pinfunction "IO32_8") (pintype "unspecified"))
      (node (ref "USER1") (pin "3") (pinfunction "3_3") (pintype "unspecified"))
    )
    (net (code "33") (name "/UIO3") (class "Default")
      (node (ref "U4") (pin "5") (pinfunction "SENSOR_VN_5") (pintype "unspecified"))
      (node (ref "USER2") (pin "1") (pinfunction "1_1") (pintype "unspecified"))
    )
    (net (code "34") (name "/UIO4") (class "Default")
      (node (ref "U4") (pin "9") (pinfunction "IO33_9") (pintype "unspecified"))
      (node (ref "USER2") (pin "2") (pinfunction "2_2") (pintype "unspecified"))
    )
    (net (code "35") (name "/UIO5") (class "Default")
      (node (ref "U4") (pin "6") (pinfunction "IO34_6") (pintype "unspecified"))
      (node (ref "USER2") (pin "3") (pinfunction "3_3") (pintype "unspecified"))
    )
    (net (code "36") (name "/VFAN") (class "Default")
      (node (ref "SYSFAN1") (pin "2") (pinfunction "2_2") (pintype "bidirectional"))
      (node (ref "VFAN") (pin "2") (pinfunction "2_2") (pintype "unspecified"))
    )
    (net (code "37") (name "/VPD") (class "Default")
      (node (ref "20V") (pin "2") (pinfunction "2_2") (pintype "unspecified"))
      (node (ref "C1") (pin "1") (pinfunction "1_1") (pintype "unspecified"))
      (node (ref "C15") (pin "2") (pinfunction "2_2") (pintype "input"))
      (node (ref "C16") (pin "2") (pinfunction "2_2") (pintype "input"))
      (node (ref "C18") (pin "1") (pinfunction "1_1") (pintype "unspecified"))
      (node (ref "C3") (pin "2") (pinfunction "2_2") (pintype "input"))
      (node (ref "C4") (pin "1") (pinfunction "1_1") (pintype "unspecified"))
      (node (ref "PD") (pin "A4B9") (pinfunction "VBUS_A4B9") (pintype "unspecified"))
      (node (ref "PD") (pin "A9B4") (pinfunction "VBUS_A9B4") (pintype "unspecified"))
      (node (ref "R17") (pin "2") (pinfunction "2_2") (pintype "input"))
      (node (ref "R18") (pin "2") (pinfunction "2_2") (pintype "input"))
      (node (ref "U2") (pin "11") (pinfunction "VM_11") (pintype "unspecified"))
      (node (ref "U2") (pin "4") (pinfunction "VM_4") (pintype "unspecified"))
      (node (ref "U7") (pin "7") (pinfunction "VIN_7") (pintype "unspecified"))
    )
    (net (code "38") (name "/VTEMP") (class "Default")
      (node (ref "C6") (pin "1") (pinfunction "1_1") (pintype "unspecified"))
      (node (ref "U3") (pin "2") (pinfunction "VOUT_2") (pintype "unspecified"))
      (node (ref "U4") (pin "4") (pinfunction "SENSOR_VP_4") (pintype "unspecified"))
    )
    (net (code "39") (name "Net-(C9-Pad1)") (class "Default")
      (node (ref "C9") (pin "1") (pinfunction "1_1") (pintype "input"))
      (node (ref "U8") (pin "18") (pinfunction "NC_18") (pintype "unspecified"))
    )
    (net (code "40") (name "Net-(D1-A)") (class "Default")
      (node (ref "D1") (pin "1") (pinfunction "A_1") (pintype "unspecified"))
      (node (ref "U5") (pin "2") (pinfunction "VOUT_2") (pintype "unspecified"))
      (node (ref "U5") (pin "4") (pinfunction "VOUT_4") (pintype "unspecified"))
    )
    (net (code "41") (name "Net-(D2-K)") (class "Default")
      (node (ref "C21") (pin "1") (pinfunction "1_1") (pintype "unspecified"))
      (node (ref "D2") (pin "1") (pinfunction "K_1") (pintype "unspecified"))
      (node (ref "L1") (pin "2") (pinfunction "2_2") (pintype "unspecified"))
      (node (ref "U7") (pin "8") (pinfunction "PH_8") (pintype "unspecified"))
    )
    (net (code "42") (name "Net-(DATA-CC1)") (class "Default")
      (node (ref "DATA") (pin "A5") (pinfunction "CC1_A5") (pintype "unspecified"))
      (node (ref "R22") (pin "1") (pinfunction "1_1") (pintype "input"))
    )
    (net (code "43") (name "Net-(DATA-CC2)") (class "Default")
      (node (ref "DATA") (pin "B5") (pinfunction "CC2_B5") (pintype "unspecified"))
      (node (ref "R20") (pin "2") (pinfunction "2_2") (pintype "input"))
    )
    (net (code "44") (name "Net-(PWR-K)") (class "Default")
      (node (ref "PWR") (pin "2") (pinfunction "K_2") (pintype "unspecified"))
      (node (ref "R19") (pin "2") (pinfunction "2_2") (pintype "input"))
    )
    (net (code "45") (name "Net-(Q1-B)") (class "Default")
      (node (ref "Q1") (pin "1") (pinfunction "B_1") (pintype "unspecified"))
      (node (ref "R2") (pin "2") (pinfunction "2_2") (pintype "input"))
    )
    (net (code "46") (name "Net-(Q2-B)") (class "Default")
      (node (ref "Q2") (pin "1") (pinfunction "B_1") (pintype "unspecified"))
      (node (ref "R3") (pin "1") (pinfunction "1_1") (pintype "input"))
    )
    (net (code "47") (name "Net-(R23-Pad1)") (class "Default")
      (node (ref "R23") (pin "1") (pinfunction "1_1") (pintype "input"))
      (node (ref "R24") (pin "2") (pinfunction "2_2") (pintype "input"))
    )
    (net (code "48") (name "Net-(U2-CP1)") (class "Default")
      (node (ref "C12") (pin "2") (pinfunction "2_2") (pintype "unspecified"))
      (node (ref "U2") (pin "1") (pinfunction "CP1_1") (pintype "unspecified"))
    )
    (net (code "49") (name "Net-(U2-CP2)") (class "Default")
      (node (ref "C12") (pin "1") (pinfunction "1_1") (pintype "unspecified"))
      (node (ref "U2") (pin "2") (pinfunction "CP2_2") (pintype "unspecified"))
    )
    (net (code "50") (name "Net-(U2-V3P3OUT)") (class "Default")
      (node (ref "C5") (pin "2") (pinfunction "2_2") (pintype "unspecified"))
      (node (ref "U2") (pin "15") (pinfunction "V3P3OUT_15") (pintype "unspecified"))
    )
    (net (code "51") (name "Net-(U2-VCP)") (class "Default")
      (node (ref "C18") (pin "2") (pinfunction "2_2") (pintype "unspecified"))
      (node (ref "U2") (pin "3") (pinfunction "VCP_3") (pintype "unspecified"))
    )
    (net (code "52") (name "Net-(U7-BOOT)") (class "Default")
      (node (ref "C21") (pin "2") (pinfunction "2_2") (pintype "unspecified"))
      (node (ref "U7") (pin "1") (pinfunction "BOOT_1") (pintype "unspecified"))
    )
    (net (code "53") (name "Net-(U7-VSENSE)") (class "Default")
      (node (ref "R21") (pin "1") (pinfunction "1_1") (pintype "input"))
      (node (ref "R23") (pin "2") (pinfunction "2_2") (pintype "input"))
      (node (ref "U7") (pin "4") (pinfunction "VSENSE_4") (pintype "unspecified"))
    )
    (net (code "54") (name "Net-(U9-VBUS)") (class "Default")
      (node (ref "R17") (pin "1") (pinfunction "1_1") (pintype "input"))
      (node (ref "U9") (pin "8") (pinfunction "VBUS_8") (pintype "unspecified"))
    )
    (net (code "55") (name "Net-(U9-VDD)") (class "Default")
      (node (ref "C8") (pin "2") (pinfunction "2_2") (pintype "unspecified"))
      (node (ref "R18") (pin "1") (pinfunction "1_1") (pintype "input"))
      (node (ref "U9") (pin "1") (pinfunction "VDD_1") (pintype "unspecified"))
    )
    (net (code "56") (name "unconnected-(DATA-Pad12)") (class "Default")
      (node (ref "DATA") (pin "12") (pinfunction "12_12") (pintype "unspecified+no_connect"))
    )
    (net (code "57") (name "unconnected-(DATA-Pad13)") (class "Default")
      (node (ref "DATA") (pin "13") (pinfunction "13_13") (pintype "unspecified+no_connect"))
    )
    (net (code "58") (name "unconnected-(DATA-Pad14)") (class "Default")
      (node (ref "DATA") (pin "14") (pinfunction "14_14") (pintype "unspecified+no_connect"))
    )
    (net (code "59") (name "unconnected-(DATA-Pad15)") (class "Default")
      (node (ref "DATA") (pin "15") (pinfunction "15_15") (pintype "unspecified+no_connect"))
    )
    (net (code "60") (name "unconnected-(DATA-SBU1-PadA8)") (class "Default")
      (node (ref "DATA") (pin "A8") (pinfunction "SBU1_A8") (pintype "unspecified+no_connect"))
    )
    (net (code "61") (name "unconnected-(DATA-SBU2-PadB8)") (class "Default")
      (node (ref "DATA") (pin "B8") (pinfunction "SBU2_B8") (pintype "unspecified+no_connect"))
    )
    (net (code "62") (name "unconnected-(PD-DN1-PadA7)") (class "Default")
      (node (ref "PD") (pin "A7") (pinfunction "DN1_A7") (pintype "unspecified+no_connect"))
    )
    (net (code "63") (name "unconnected-(PD-DN2-PadB7)") (class "Default")
      (node (ref "PD") (pin "B7") (pinfunction "DN2_B7") (pintype "unspecified+no_connect"))
    )
    (net (code "64") (name "unconnected-(PD-DP1-PadA6)") (class "Default")
      (node (ref "PD") (pin "A6") (pinfunction "DP1_A6") (pintype "unspecified+no_connect"))
    )
    (net (code "65") (name "unconnected-(PD-DP2-PadB6)") (class "Default")
      (node (ref "PD") (pin "B6") (pinfunction "DP2_B6") (pintype "unspecified+no_connect"))
    )
    (net (code "66") (name "unconnected-(PD-Pad12)") (class "Default")
      (node (ref "PD") (pin "12") (pinfunction "12_12") (pintype "unspecified+no_connect"))
    )
    (net (code "67") (name "unconnected-(PD-Pad13)") (class "Default")
      (node (ref "PD") (pin "13") (pinfunction "13_13") (pintype "unspecified+no_connect"))
    )
    (net (code "68") (name "unconnected-(PD-Pad14)") (class "Default")
      (node (ref "PD") (pin "14") (pinfunction "14_14") (pintype "unspecified+no_connect"))
    )
    (net (code "69") (name "unconnected-(PD-Pad15)") (class "Default")
      (node (ref "PD") (pin "15") (pinfunction "15_15") (pintype "unspecified+no_connect"))
    )
    (net (code "70") (name "unconnected-(PD-SBU1-PadA8)") (class "Default")
      (node (ref "PD") (pin "A8") (pinfunction "SBU1_A8") (pintype "unspecified+no_connect"))
    )
    (net (code "71") (name "unconnected-(PD-SBU2-PadB8)") (class "Default")
      (node (ref "PD") (pin "B8") (pinfunction "SBU2_B8") (pintype "unspecified+no_connect"))
    )
    (net (code "72") (name "unconnected-(SYSFAN1-Pad3)") (class "Default")
      (node (ref "SYSFAN1") (pin "3") (pinfunction "3_3") (pintype "bidirectional+no_connect"))
    )
    (net (code "73") (name "unconnected-(SYSFAN1-Pad4)") (class "Default")
      (node (ref "SYSFAN1") (pin "4") (pinfunction "4_4") (pintype "bidirectional+no_connect"))
    )
    (net (code "74") (name "unconnected-(U1-EP-Pad17)") (class "Default")
      (node (ref "U1") (pin "17") (pinfunction "EP_17") (pintype "unspecified+no_connect"))
    )
    (net (code "75") (name "unconnected-(U1-NC-Pad1)") (class "Default")
      (node (ref "U1") (pin "1") (pinfunction "NC_1") (pintype "unspecified+no_connect"))
    )
    (net (code "76") (name "unconnected-(U1-NC-Pad2)") (class "Default")
      (node (ref "U1") (pin "2") (pinfunction "NC_2") (pintype "unspecified+no_connect"))
    )
    (net (code "77") (name "unconnected-(U1-NC-Pad3)") (class "Default")
      (node (ref "U1") (pin "3") (pinfunction "NC_3") (pintype "unspecified+no_connect"))
    )
    (net (code "78") (name "unconnected-(U1-NC-Pad4)") (class "Default")
      (node (ref "U1") (pin "4") (pinfunction "NC_4") (pintype "unspecified+no_connect"))
    )
    (net (code "79") (name "unconnected-(U1-NC-Pad10)") (class "Default")
      (node (ref "U1") (pin "10") (pinfunction "NC_10") (pintype "unspecified+no_connect"))
    )
    (net (code "80") (name "unconnected-(U1-OUT-Pad15)") (class "Default")
      (node (ref "U1") (pin "15") (pinfunction "OUT_15") (pintype "unspecified+no_connect"))
    )
    (net (code "81") (name "unconnected-(U1-PUSH-Pad5)") (class "Default")
      (node (ref "U1") (pin "5") (pinfunction "PUSH_5") (pintype "unspecified+no_connect"))
    )
    (net (code "82") (name "unconnected-(U1-U-Pad11)") (class "Default")
      (node (ref "U1") (pin "11") (pinfunction "U_11") (pintype "unspecified+no_connect"))
    )
    (net (code "83") (name "unconnected-(U1-V-Pad12)") (class "Default")
      (node (ref "U1") (pin "12") (pinfunction "V_12") (pintype "unspecified+no_connect"))
    )
    (net (code "84") (name "unconnected-(U1-W-Pad9)") (class "Default")
      (node (ref "U1") (pin "9") (pinfunction "W_9") (pintype "unspecified+no_connect"))
    )
    (net (code "85") (name "unconnected-(U2-COMPO#-Pad19)") (class "Default")
      (node (ref "U2") (pin "19") (pinfunction "COMPO#_19") (pintype "unspecified+no_connect"))
    )
    (net (code "86") (name "unconnected-(U2-NC-Pad21)") (class "Default")
      (node (ref "U2") (pin "21") (pinfunction "NC_21") (pintype "unspecified+no_connect"))
    )
    (net (code "87") (name "unconnected-(U4-IO2-Pad24)") (class "Default")
      (node (ref "U4") (pin "24") (pinfunction "IO2_24") (pintype "unspecified+no_connect"))
    )
    (net (code "88") (name "unconnected-(U4-IO5-Pad29)") (class "Default")
      (node (ref "U4") (pin "29") (pinfunction "IO5_29") (pintype "unspecified+no_connect"))
    )
    (net (code "89") (name "unconnected-(U4-IO12-Pad14)") (class "Default")
      (node (ref "U4") (pin "14") (pinfunction "IO12_14") (pintype "unspecified+no_connect"))
    )
    (net (code "90") (name "unconnected-(U4-IO13-Pad16)") (class "Default")
      (node (ref "U4") (pin "16") (pinfunction "IO13_16") (pintype "unspecified+no_connect"))
    )
    (net (code "91") (name "unconnected-(U4-IO15-Pad23)") (class "Default")
      (node (ref "U4") (pin "23") (pinfunction "IO15_23") (pintype "unspecified+no_connect"))
    )
    (net (code "92") (name "unconnected-(U4-IO16-Pad27)") (class "Default")
      (node (ref "U4") (pin "27") (pinfunction "IO16_27") (pintype "unspecified+no_connect"))
    )
    (net (code "93") (name "unconnected-(U4-IO17-Pad28)") (class "Default")
      (node (ref "U4") (pin "28") (pinfunction "IO17_28") (pintype "unspecified+no_connect"))
    )
    (net (code "94") (name "unconnected-(U4-IO18-Pad30)") (class "Default")
      (node (ref "U4") (pin "30") (pinfunction "IO18_30") (pintype "unspecified+no_connect"))
    )
    (net (code "95") (name "unconnected-(U4-IO19-Pad31)") (class "Default")
      (node (ref "U4") (pin "31") (pinfunction "IO19_31") (pintype "unspecified+no_connect"))
    )
    (net (code "96") (name "unconnected-(U4-NC-Pad17)") (class "Default")
      (node (ref "U4") (pin "17") (pinfunction "NC_17") (pintype "unspecified+no_connect"))
    )
    (net (code "97") (name "unconnected-(U4-NC-Pad18)") (class "Default")
      (node (ref "U4") (pin "18") (pinfunction "NC_18") (pintype "unspecified+no_connect"))
    )
    (net (code "98") (name "unconnected-(U4-NC-Pad19)") (class "Default")
      (node (ref "U4") (pin "19") (pinfunction "NC_19") (pintype "unspecified+no_connect"))
    )
    (net (code "99") (name "unconnected-(U4-NC-Pad20)") (class "Default")
      (node (ref "U4") (pin "20") (pinfunction "NC_20") (pintype "unspecified+no_connect"))
    )
    (net (code "100") (name "unconnected-(U4-NC-Pad21)") (class "Default")
      (node (ref "U4") (pin "21") (pinfunction "NC_21") (pintype "unspecified+no_connect"))
    )
    (net (code "101") (name "unconnected-(U4-NC-Pad22)") (class "Default")
      (node (ref "U4") (pin "22") (pinfunction "NC_22") (pintype "unspecified+no_connect"))
    )
    (net (code "102") (name "unconnected-(U4-NC-Pad32)") (class "Default")
      (node (ref "U4") (pin "32") (pinfunction "NC_32") (pintype "unspecified+no_connect"))
    )
    (net (code "103") (name "unconnected-(U7-ENA-Pad5)") (class "Default")
      (node (ref "U7") (pin "5") (pinfunction "ENA_5") (pintype "unspecified+no_connect"))
    )
    (net (code "104") (name "unconnected-(U7-NC-Pad2)") (class "Default")
      (node (ref "U7") (pin "2") (pinfunction "NC_2") (pintype "unspecified+no_connect"))
    )
    (net (code "105") (name "unconnected-(U7-NC-Pad3)") (class "Default")
      (node (ref "U7") (pin "3") (pinfunction "NC_3") (pintype "unspecified+no_connect"))
    )
    (net (code "106") (name "unconnected-(U8-CTS-Pad23)") (class "Default")
      (node (ref "U8") (pin "23") (pinfunction "CTS_23") (pintype "unspecified+no_connect"))
    )
    (net (code "107") (name "unconnected-(U8-DCD-Pad1)") (class "Default")
      (node (ref "U8") (pin "1") (pinfunction "DCD_1") (pintype "unspecified+no_connect"))
    )
    (net (code "108") (name "unconnected-(U8-DSR-Pad27)") (class "Default")
      (node (ref "U8") (pin "27") (pinfunction "DSR_27") (pintype "unspecified+no_connect"))
    )
    (net (code "109") (name "unconnected-(U8-NC-Pad10)") (class "Default")
      (node (ref "U8") (pin "10") (pinfunction "NC_10") (pintype "unspecified+no_connect"))
    )
    (net (code "110") (name "unconnected-(U8-NC-Pad13)") (class "Default")
      (node (ref "U8") (pin "13") (pinfunction "NC_13") (pintype "unspecified+no_connect"))
    )
    (net (code "111") (name "unconnected-(U8-NC-Pad14)") (class "Default")
      (node (ref "U8") (pin "14") (pinfunction "NC_14") (pintype "unspecified+no_connect"))
    )
    (net (code "112") (name "unconnected-(U8-NC-Pad15)") (class "Default")
      (node (ref "U8") (pin "15") (pinfunction "NC_15") (pintype "unspecified+no_connect"))
    )
    (net (code "113") (name "unconnected-(U8-NC-Pad16)") (class "Default")
      (node (ref "U8") (pin "16") (pinfunction "NC_16") (pintype "unspecified+no_connect"))
    )
    (net (code "114") (name "unconnected-(U8-NC-Pad17)") (class "Default")
      (node (ref "U8") (pin "17") (pinfunction "NC_17") (pintype "unspecified+no_connect"))
    )
    (net (code "115") (name "unconnected-(U8-NC-Pad19)") (class "Default")
      (node (ref "U8") (pin "19") (pinfunction "NC_19") (pintype "unspecified+no_connect"))
    )
    (net (code "116") (name "unconnected-(U8-NC-Pad20)") (class "Default")
      (node (ref "U8") (pin "20") (pinfunction "NC_20") (pintype "unspecified+no_connect"))
    )
    (net (code "117") (name "unconnected-(U8-NC-Pad21)") (class "Default")
      (node (ref "U8") (pin "21") (pinfunction "NC_21") (pintype "unspecified+no_connect"))
    )
    (net (code "118") (name "unconnected-(U8-NC-Pad22)") (class "Default")
      (node (ref "U8") (pin "22") (pinfunction "NC_22") (pintype "unspecified+no_connect"))
    )
    (net (code "119") (name "unconnected-(U8-RI-Pad2)") (class "Default")
      (node (ref "U8") (pin "2") (pinfunction "RI_2") (pintype "unspecified+no_connect"))
    )
    (net (code "120") (name "unconnected-(U8-SUSPEND#-Pad11)") (class "Default")
      (node (ref "U8") (pin "11") (pinfunction "SUSPEND#_11") (pintype "unspecified+no_connect"))
    )
    (net (code "121") (name "unconnected-(U8-SUSPEND-Pad12)") (class "Default")
      (node (ref "U8") (pin "12") (pinfunction "SUSPEND_12") (pintype "unspecified+no_connect"))
    )
    (net (code "122") (name "unconnected-(U9-CFG1-Pad9)") (class "Default")
      (node (ref "U9") (pin "9") (pinfunction "CFG1_9") (pintype "unspecified+no_connect"))
    )
    (net (code "123") (name "unconnected-(U9-CFG2-Pad2)") (class "Default")
      (node (ref "U9") (pin "2") (pinfunction "CFG2_2") (pintype "unspecified+no_connect"))
    )
    (net (code "124") (name "unconnected-(U9-CFG3-Pad3)") (class "Default")
      (node (ref "U9") (pin "3") (pinfunction "CFG3_3") (pintype "unspecified+no_connect"))
    )
    (net (code "125") (name "unconnected-(U9-DM-Pad5)") (class "Default")
      (node (ref "U9") (pin "5") (pinfunction "DM_5") (pintype "unspecified+no_connect"))
    )
    (net (code "126") (name "unconnected-(U9-DP-Pad4)") (class "Default")
      (node (ref "U9") (pin "4") (pinfunction "DP_4") (pintype "unspecified+no_connect"))
    )
    (net (code "127") (name "unconnected-(U9-PG-Pad10)") (class "Default")
      (node (ref "U9") (pin "10") (pinfunction "PG_10") (pintype "unspecified+no_connect"))
    )
  )
)
